# 780-00029_rev3_Pg1_Backplane_Instrument_.net
KiCad netlist of a schematic drawn in Altium Designer
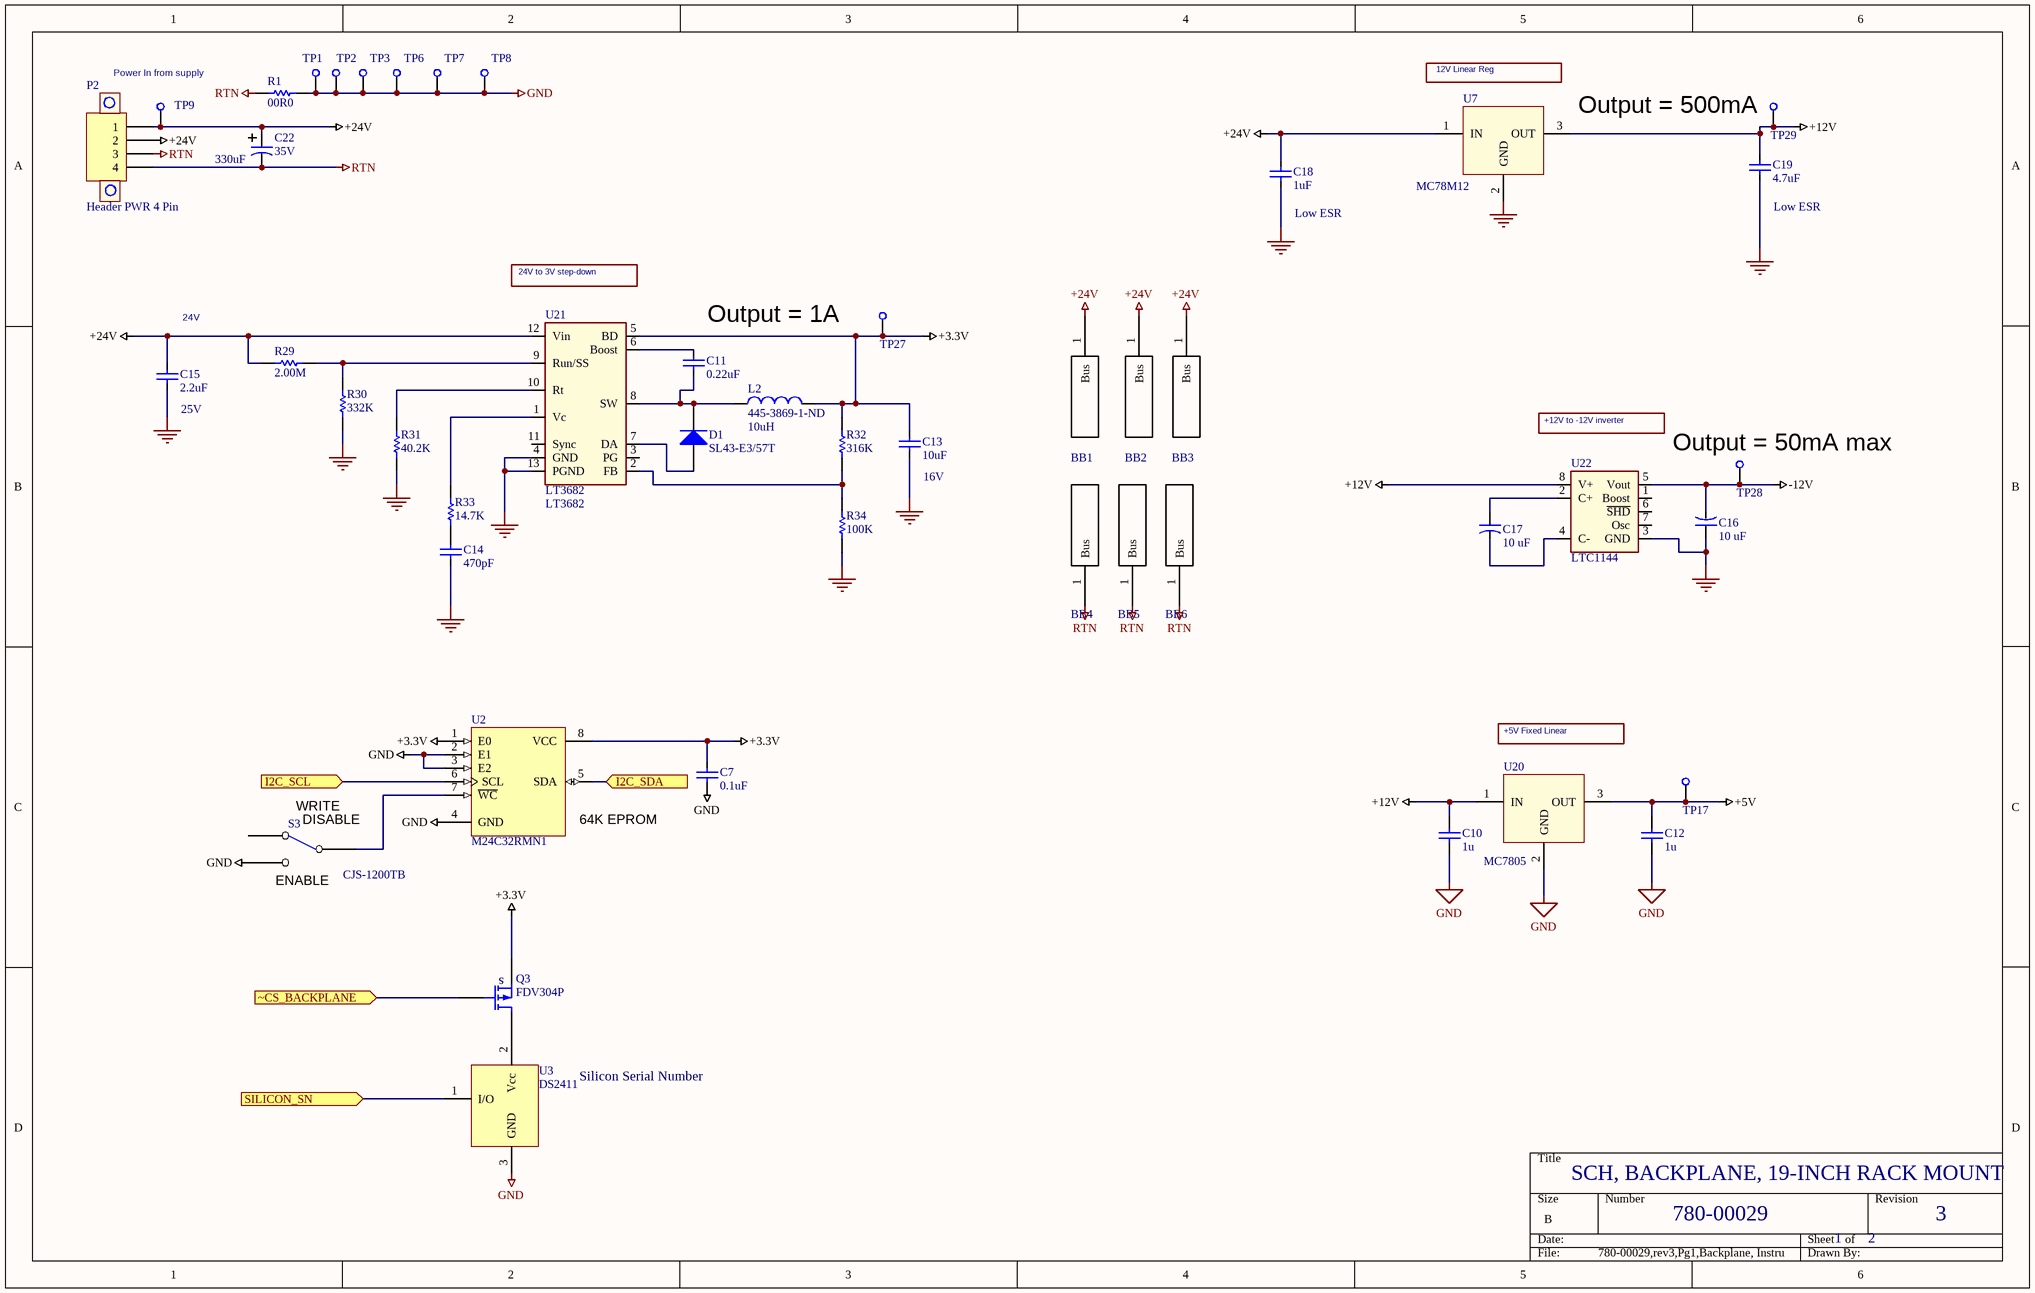
[diagram p0: 780-00029,rev3,Pg1,Backplane, Instrument Crate.SchDoc]

(export (version "E")
  (design (tool "Eeschema 10.0.6"))
  (components
    (comp (ref "BB1")
      (value "Bus Bar")
      (footprint "Bus Bar 1.5\" pitch")
      (fields (field (name "MANUFACTURER") "Circuit Components Inc."))
      (libsource (lib "Richs Schematic Components") (part "Bus Bar"))
    )
    (comp (ref "BB2")
      (value "Bus Bar")
      (footprint "Bus Bar 1.5\" pitch")
      (fields (field (name "MANUFACTURER") "Circuit Components Inc."))
      (libsource (lib "Richs Schematic Components") (part "Bus Bar"))
    )
    (comp (ref "BB3")
      (value "Bus Bar")
      (footprint "Bus Bar 1.5\" pitch")
      (fields (field (name "MANUFACTURER") "Circuit Components Inc."))
      (libsource (lib "Richs Schematic Components") (part "Bus Bar"))
    )
    (comp (ref "BB4")
      (value "Bus Bar")
      (footprint "Bus Bar 1.5\" pitch")
      (fields (field (name "MANUFACTURER") "Circuit Components Inc."))
      (libsource (lib "Richs Schematic Components") (part "Bus Bar"))
    )
    (comp (ref "BB5")
      (value "Bus Bar")
      (footprint "Bus Bar 1.5\" pitch")
      (fields (field (name "MANUFACTURER") "Circuit Components Inc."))
      (libsource (lib "Richs Schematic Components") (part "Bus Bar"))
    )
    (comp (ref "BB6")
      (value "Bus Bar")
      (footprint "Bus Bar 1.5\" pitch")
      (fields (field (name "MANUFACTURER") "Circuit Components Inc."))
      (libsource (lib "Richs Schematic Components") (part "Bus Bar"))
    )
    (comp (ref "C7")
      (value "0.1uF")
      (footprint "SMD_0805")
      (description "Capacitor")
      (fields (field (name "MANUFACTURER") "AVX") (field (name "Comment") "Cap SMD"))
      (libsource (lib "Richs Schematic Components") (part "Cap SMD"))
    )
    (comp (ref "C10")
      (value "1u")
      (footprint "2012[0805]")
      (description "Capacitor")
      (fields (field (name "MANUFACTURER") "Taiyo Yuden"))
      (libsource (lib "Miscellaneous Devices") (part "Cap"))
    )
    (comp (ref "C11")
      (value "0.22uF")
      (footprint "SMD_0805")
      (description "Capacitor")
      (fields (field (name "Comment") "Cap SMD"))
      (libsource (lib "Richs Schematic Components") (part "Cap SMD"))
    )
    (comp (ref "C12")
      (value "1u")
      (footprint "2012[0805]")
      (description "Capacitor")
      (fields (field (name "MANUFACTURER") "Taiyo Yuden"))
      (libsource (lib "Miscellaneous Devices") (part "Cap"))
    )
    (comp (ref "C13")
      (value "16V")
      (footprint "SMD_0805")
      (description "Capacitor")
      (fields (field (name "ALTIUM_VALUE") "10uF"))
      (libsource (lib "Richs Schematic Components") (part "Cap SMD"))
    )
    (comp (ref "C14")
      (value "470pF")
      (footprint "SMD_0805")
      (description "Capacitor")
      (fields (field (name "Comment") "Cap SMD"))
      (libsource (lib "Richs Schematic Components") (part "Cap SMD"))
    )
    (comp (ref "C15")
      (value "25V")
      (footprint "SMD_0805")
      (description "Capacitor")
      (fields (field (name "MANUFACTURER") "Taiyo Yuden") (field (name "ALTIUM_VALUE") "2.2uF"))
      (libsource (lib "Richs Schematic Components") (part "Cap SMD"))
    )
    (comp (ref "C16")
      (value "10 uF")
      (footprint "SMD_CAP_3216")
      (description "outline 3.2mm x 1.6mm")
      (fields (field (name "MANUFACTURER") "KEMET") (field (name "Comment") "16V"))
      (libsource (lib "Richs Schematic Components") (part "Cap Tant 16V"))
    )
    (comp (ref "C17")
      (value "10 uF")
      (footprint "SMD_CAP_3216")
      (description "outline 3.2mm x 1.6mm")
      (fields (field (name "MANUFACTURER") "KEMET") (field (name "Comment") "16V"))
      (libsource (lib "Richs Schematic Components") (part "Cap Tant 16V"))
    )
    (comp (ref "C18")
      (value "Low ESR")
      (footprint "SMD_1206")
      (description "Capacitor")
      (fields (field (name "MANUFACTURER") "TDK") (field (name "ALTIUM_VALUE") "1uF"))
      (libsource (lib "Richs Schematic Components") (part "Cap SMD"))
    )
    (comp (ref "C19")
      (value "Low ESR")
      (footprint "SMD_1206")
      (description "Capacitor")
      (fields (field (name "MANUFACTURER") "TDK") (field (name "ALTIUM_VALUE") "4.7uF"))
      (libsource (lib "Richs Schematic Components") (part "Cap SMD"))
    )
    (comp (ref "C22")
      (value "35V")
      (footprint "CAP, Thru Hole 10mm dia")
      (description "Radial Thru hole")
      (fields (field (name "ALTIUM_VALUE") "330uF"))
      (libsource (lib "Richs Schematic Components") (part "Cap Elec, 330 uF, 35V"))
    )
    (comp (ref "D1")
      (value "SL43-E3/57T")
      (footprint "DO-214AB")
      (description "Default Diode")
      (fields (field (name "MANUFACTURER") "Vishay/Dale"))
      (libsource (lib "Miscellaneous Devices") (part "Diode"))
    )
    (comp (ref "L2")
      (value "445-3869-1-ND")
      (footprint "Inductor TDC SLF")
      (description "Inductor")
      (fields (field (name "MANUFACTURER") "TDK") (field (name "ALTIUM_VALUE") "10uH"))
      (libsource (lib "Richs Schematic Components") (part "Inductor SMD 10uH 1.8A"))
    )
    (comp (ref "P2")
      (value "Header PWR 4 Pin")
      (footprint "HDR-4 pin w/screw")
      (description "Header, 4-Pin")
      (fields (field (name "MANUFACTURER") "tyco"))
      (libsource (lib "Richs Schematic Components") (part "Header 4 PWR"))
    )
    (comp (ref "Q3")
      (value "FDV304P")
      (footprint "SMD_SOT23_3")
      (description "P-MOSFET LOGIC LEVEL")
      (fields (field (name "MANUFACTURER") "Fairchild"))
      (libsource (lib "Richs Schematic Components") (part "FDV304P"))
    )
    (comp (ref "R1")
      (value "00R0")
      (footprint "SMD_0805")
      (description "Resistor 0805")
      (fields (field (name "MANUFACTURER") "Vishay/Dale") (field (name "Comment") "Res 0805"))
      (libsource (lib "Richs Schematic Components") (part "Res SMD"))
    )
    (comp (ref "R29")
      (value "2.00M")
      (footprint "SMD_0805")
      (description "Resistor 0805")
      (fields (field (name "MANUFACTURER") "Vishay/Dale") (field (name "Comment") "Res 0805"))
      (libsource (lib "Richs Schematic Components") (part "Res SMD"))
    )
    (comp (ref "R30")
      (value "332K")
      (footprint "SMD_0805")
      (description "Resistor 0805")
      (fields (field (name "MANUFACTURER") "Vishay/Dale") (field (name "Comment") "Res 0805"))
      (libsource (lib "Richs Schematic Components") (part "Res SMD"))
    )
    (comp (ref "R31")
      (value "40.2K")
      (footprint "SMD_0805")
      (description "Resistor 0805")
      (fields (field (name "MANUFACTURER") "Vishay/Dale") (field (name "Comment") "Res 0805"))
      (libsource (lib "Richs Schematic Components") (part "Res SMD"))
    )
    (comp (ref "R32")
      (value "316K")
      (footprint "SMD_0805")
      (description "Resistor 0805")
      (fields (field (name "MANUFACTURER") "Vishay/Dale") (field (name "Comment") "Res 0805"))
      (libsource (lib "Richs Schematic Components") (part "Res SMD"))
    )
    (comp (ref "R33")
      (value "14.7K")
      (footprint "SMD_0805")
      (description "Resistor 0805")
      (fields (field (name "MANUFACTURER") "Vishay/Dale") (field (name "Comment") "Res 0805"))
      (libsource (lib "Richs Schematic Components") (part "Res SMD"))
    )
    (comp (ref "R34")
      (value "100K")
      (footprint "SMD_0805")
      (description "Resistor 0805")
      (fields (field (name "MANUFACTURER") "Vishay/Dale") (field (name "Comment") "Res 0805"))
      (libsource (lib "Richs Schematic Components") (part "Res SMD"))
    )
    (comp (ref "S3")
      (value "CJS-1200TB")
      (footprint "CAS-120B")
      (fields (field (name "MANUFACTURER") "Copal Electronics"))
      (libsource (lib "JON_1_Library") (part "SW_SPDT_DOUG"))
    )
    (comp (ref "TP1")
      (value "Test point")
      (footprint "Protel 99SE BANKS PCB:PAD_80D_052H")
      (description "Test Point")
      (fields (field (name "MANUFACTURER") "Keystone"))
      (libsource (lib "Richs Schematic Components") (part "Test point"))
    )
    (comp (ref "TP2")
      (value "Test point")
      (footprint "Protel 99SE BANKS PCB:PAD_80D_052H")
      (description "Test Point")
      (fields (field (name "MANUFACTURER") "Keystone"))
      (libsource (lib "Richs Schematic Components") (part "Test point"))
    )
    (comp (ref "TP3")
      (value "Test point")
      (footprint "Protel 99SE BANKS PCB:PAD_80D_052H")
      (description "Test Point")
      (fields (field (name "MANUFACTURER") "Keystone"))
      (libsource (lib "Richs Schematic Components") (part "Test point"))
    )
    (comp (ref "TP6")
      (value "Test point")
      (footprint "Protel 99SE BANKS PCB:PAD_80D_052H")
      (description "Test Point")
      (fields (field (name "MANUFACTURER") "Keystone"))
      (libsource (lib "Richs Schematic Components") (part "Test point"))
    )
    (comp (ref "TP7")
      (value "Test point")
      (footprint "Protel 99SE BANKS PCB:PAD_80D_052H")
      (description "Test Point")
      (fields (field (name "MANUFACTURER") "Keystone"))
      (libsource (lib "Richs Schematic Components") (part "Test point"))
    )
    (comp (ref "TP8")
      (value "Test point")
      (footprint "Protel 99SE BANKS PCB:PAD_80D_052H")
      (description "Test Point")
      (fields (field (name "MANUFACTURER") "Keystone"))
      (libsource (lib "Richs Schematic Components") (part "Test point"))
    )
    (comp (ref "TP9")
      (value "Test Point SMD")
      (footprint "SMD_TEST POINT")
      (description "SMD loop test point")
      (libsource (lib "Richs Schematic Components") (part "Test Point SMD"))
    )
    (comp (ref "TP17")
      (value "Test Point SMD")
      (footprint "SMD_TEST POINT")
      (description "SMD loop test point")
      (libsource (lib "Richs Schematic Components") (part "Test Point SMD"))
    )
    (comp (ref "TP27")
      (value "Test Point SMD")
      (footprint "SMD_TEST POINT")
      (description "SMD loop test point")
      (libsource (lib "Richs Schematic Components") (part "Test Point SMD"))
    )
    (comp (ref "TP28")
      (value "Test Point SMD")
      (footprint "SMD_TEST POINT")
      (description "SMD loop test point")
      (libsource (lib "Richs Schematic Components") (part "Test Point SMD"))
    )
    (comp (ref "TP29")
      (value "Test Point SMD")
      (footprint "SMD_TEST POINT")
      (description "SMD loop test point")
      (libsource (lib "Richs Schematic Components") (part "Test Point SMD"))
    )
    (comp (ref "U2")
      (value "M24C32RMN1")
      (footprint "SOP8_N")
      (description "32 Kbit Serial I²C Bus EEPROM")
      (libsource (lib "ST Memory EEPROM Serial") (part "M24C32RMN1"))
    )
    (comp (ref "U3")
      (value "DS2411")
      (footprint "SMD_SOT23_3")
      (description "Silicon Serial Number")
      (fields (field (name "MANUFACTURER") "MAXIM"))
      (libsource (lib "Richs Schematic Components") (part "DS2411"))
    )
    (comp (ref "U7")
      (value "MC78M12")
      (footprint "TO-252(D-PAK)  PowerPAD")
      (fields (field (name "MANUFACTURER") "On Semi") (field (name "Comment") "Voltage Reg, Fixed"))
      (libsource (lib "Richs Schematic Components") (part "Voltage Reg, Fixed"))
    )
    (comp (ref "U20")
      (value "MC7805")
      (footprint "TO-252(D-PAK)  PowerPAD")
      (description "MC78M05")
      (fields (field (name "MANUFACTURER") "Fairchild") (field (name "Comment") "Voltage Reg, Fixed"))
      (libsource (lib "Richs Schematic Components") (part "Voltage Reg, Fixed"))
    )
    (comp (ref "U21")
      (value "LT3682")
      (footprint "DD12/DFN12")
      (description "1A uPwr Step-Down switching regulator")
      (fields (field (name "MANUFACTURER") "Linear") (field (name "ALTIUM_VALUE") "LT3682"))
      (libsource (lib "Richs Schematic Components") (part "LT3682"))
    )
    (comp (ref "U22")
      (value "LTC1144")
      (footprint "S8_M")
      (description "IC VOLT CONV SW-CAP W/SHTDN8SOIC")
      (fields (field (name "MANUFACTURER") "Linear"))
      (libsource (lib "Richs Schematic Components") (part "LTC1144"))
    )
  )
  (nets
    (net (code "1") (name "+3.3V") (class "Default")
      (node (ref "C13") (pin "2") (pinfunction "2_2") (pintype "passive"))
      (node (ref "C7") (pin "2") (pinfunction "2_2") (pintype "passive"))
      (node (ref "L2") (pin "2") (pinfunction "2_2") (pintype "passive"))
      (node (ref "Q3") (pin "2") (pinfunction "S_2") (pintype "passive"))
      (node (ref "R32") (pin "2") (pinfunction "2_2") (pintype "passive"))
      (node (ref "TP27") (pin "1") (pinfunction "TP_1") (pintype "passive"))
      (node (ref "U2") (pin "1") (pinfunction "E0_1") (pintype "input"))
      (node (ref "U2") (pin "8") (pinfunction "VCC_8") (pintype "power_in"))
      (node (ref "U21") (pin "5") (pinfunction "BD_5") (pintype "passive"))
    )
    (net (code "2") (name "+5V") (class "Default")
      (node (ref "C12") (pin "1") (pinfunction "1_1") (pintype "passive"))
      (node (ref "TP17") (pin "1") (pinfunction "TP_1") (pintype "passive"))
      (node (ref "U20") (pin "3") (pinfunction "OUT_3") (pintype "passive"))
    )
    (net (code "3") (name "+12V") (class "Default")
      (node (ref "C10") (pin "1") (pinfunction "1_1") (pintype "passive"))
      (node (ref "C19") (pin "2") (pinfunction "2_2") (pintype "passive"))
      (node (ref "TP29") (pin "1") (pinfunction "TP_1") (pintype "passive"))
      (node (ref "U20") (pin "1") (pinfunction "IN_1") (pintype "passive"))
      (node (ref "U22") (pin "8") (pinfunction "V+_8") (pintype "power_in"))
      (node (ref "U7") (pin "3") (pinfunction "OUT_3") (pintype "passive"))
    )
    (net (code "4") (name "+24V") (class "Default")
      (node (ref "BB1") (pin "1") (pinfunction "Bus_1") (pintype "passive"))
      (node (ref "BB2") (pin "1") (pinfunction "Bus_1") (pintype "passive"))
      (node (ref "BB3") (pin "1") (pinfunction "Bus_1") (pintype "passive"))
      (node (ref "C15") (pin "2") (pinfunction "2_2") (pintype "passive"))
      (node (ref "C18") (pin "2") (pinfunction "2_2") (pintype "passive"))
      (node (ref "C22") (pin "1") (pinfunction "1_1") (pintype "passive"))
      (node (ref "P2") (pin "1") (pinfunction "1_1") (pintype "passive"))
      (node (ref "P2") (pin "2") (pinfunction "2_2") (pintype "passive"))
      (node (ref "R29") (pin "1") (pinfunction "1_1") (pintype "passive"))
      (node (ref "TP9") (pin "1") (pinfunction "TP_1") (pintype "passive"))
      (node (ref "U21") (pin "12") (pinfunction "Vin_12") (pintype "passive"))
      (node (ref "U7") (pin "1") (pinfunction "IN_1") (pintype "passive"))
    )
    (net (code "5") (name "-12V") (class "Default")
      (node (ref "C16") (pin "2") (pinfunction "2_2") (pintype "passive"))
      (node (ref "TP28") (pin "1") (pinfunction "TP_1") (pintype "passive"))
      (node (ref "U22") (pin "5") (pinfunction "Vout_5") (pintype "passive"))
    )
    (net (code "6") (name "/I2C_SCL") (class "Default")
      (node (ref "U2") (pin "6") (pinfunction "SCL_6") (pintype "input"))
    )
    (net (code "7") (name "/I2C_SDA") (class "Default")
      (node (ref "U2") (pin "5") (pinfunction "SDA_5") (pintype "bidirectional"))
    )
    (net (code "8") (name "/SILICON_SN") (class "Default")
      (node (ref "U3") (pin "1") (pinfunction "I/O_1") (pintype "passive"))
    )
    (net (code "9") (name "/~CS_BACKPLANE") (class "Default")
      (node (ref "Q3") (pin "1") (pinfunction "G_1") (pintype "passive"))
    )
    (net (code "10") (name "GND") (class "Default")
      (node (ref "C10") (pin "2") (pinfunction "2_2") (pintype "passive"))
      (node (ref "C12") (pin "2") (pinfunction "2_2") (pintype "passive"))
      (node (ref "C13") (pin "1") (pinfunction "1_1") (pintype "passive"))
      (node (ref "C14") (pin "1") (pinfunction "1_1") (pintype "passive"))
      (node (ref "C15") (pin "1") (pinfunction "1_1") (pintype "passive"))
      (node (ref "C16") (pin "1") (pinfunction "1_1") (pintype "passive"))
      (node (ref "C18") (pin "1") (pinfunction "1_1") (pintype "passive"))
      (node (ref "C19") (pin "1") (pinfunction "1_1") (pintype "passive"))
      (node (ref "C7") (pin "1") (pinfunction "1_1") (pintype "passive"))
      (node (ref "R1") (pin "2") (pinfunction "2_2") (pintype "passive"))
      (node (ref "R30") (pin "1") (pinfunction "1_1") (pintype "passive"))
      (node (ref "R31") (pin "1") (pinfunction "1_1") (pintype "passive"))
      (node (ref "R34") (pin "1") (pinfunction "1_1") (pintype "passive"))
      (node (ref "S3") (pin "1") (pinfunction "NO_1") (pintype "passive"))
      (node (ref "TP1") (pin "1") (pinfunction "TP_1") (pintype "passive"))
      (node (ref "TP2") (pin "1") (pinfunction "TP_1") (pintype "passive"))
      (node (ref "TP3") (pin "1") (pinfunction "TP_1") (pintype "passive"))
      (node (ref "TP6") (pin "1") (pinfunction "TP_1") (pintype "passive"))
      (node (ref "TP7") (pin "1") (pinfunction "TP_1") (pintype "passive"))
      (node (ref "TP8") (pin "1") (pinfunction "TP_1") (pintype "passive"))
      (node (ref "U2") (pin "2") (pinfunction "E1_2") (pintype "input"))
      (node (ref "U2") (pin "3") (pinfunction "E2_3") (pintype "input"))
      (node (ref "U2") (pin "4") (pinfunction "GND_4") (pintype "power_in"))
      (node (ref "U20") (pin "2") (pinfunction "GND_2") (pintype "passive"))
      (node (ref "U21") (pin "13") (pinfunction "PGND_13") (pintype "passive"))
      (node (ref "U21") (pin "4") (pinfunction "GND_4") (pintype "power_in"))
      (node (ref "U22") (pin "3") (pinfunction "GND_3") (pintype "passive"))
      (node (ref "U3") (pin "3") (pinfunction "GND_3") (pintype "passive"))
      (node (ref "U7") (pin "2") (pinfunction "GND_2") (pintype "passive"))
    )
    (net (code "11") (name "Net-(C14-Pad2)") (class "Default")
      (node (ref "C14") (pin "2") (pinfunction "2_2") (pintype "passive"))
      (node (ref "R33") (pin "1") (pinfunction "1_1") (pintype "passive"))
    )
    (net (code "12") (name "Net-(D1-A)") (class "Default")
      (node (ref "D1") (pin "1") (pinfunction "A_1") (pintype "passive"))
      (node (ref "U21") (pin "7") (pinfunction "DA_7") (pintype "passive"))
    )
    (net (code "13") (name "Net-(D1-K)") (class "Default")
      (node (ref "C11") (pin "1") (pinfunction "1_1") (pintype "passive"))
      (node (ref "D1") (pin "2") (pinfunction "K_2") (pintype "passive"))
      (node (ref "L2") (pin "1") (pinfunction "1_1") (pintype "passive"))
      (node (ref "U21") (pin "8") (pinfunction "SW_8") (pintype "passive"))
    )
    (net (code "14") (name "Net-(Q3-D)") (class "Default")
      (node (ref "Q3") (pin "3") (pinfunction "D_3") (pintype "passive"))
      (node (ref "U3") (pin "2") (pinfunction "Vcc_2") (pintype "passive"))
    )
    (net (code "15") (name "Net-(S3-COM)") (class "Default")
      (node (ref "S3") (pin "2") (pinfunction "COM_2") (pintype "passive"))
      (node (ref "U2") (pin "7") (pinfunction "~{WC}_7") (pintype "input"))
    )
    (net (code "16") (name "Net-(U21-Boost)") (class "Default")
      (node (ref "C11") (pin "2") (pinfunction "2_2") (pintype "passive"))
      (node (ref "U21") (pin "6") (pinfunction "Boost_6") (pintype "passive"))
    )
    (net (code "17") (name "Net-(U21-FB)") (class "Default")
      (node (ref "R32") (pin "1") (pinfunction "1_1") (pintype "passive"))
      (node (ref "R34") (pin "2") (pinfunction "2_2") (pintype "passive"))
      (node (ref "U21") (pin "2") (pinfunction "FB_2") (pintype "passive"))
    )
    (net (code "18") (name "Net-(U21-Rt)") (class "Default")
      (node (ref "R31") (pin "2") (pinfunction "2_2") (pintype "passive"))
      (node (ref "U21") (pin "10") (pinfunction "Rt_10") (pintype "passive"))
    )
    (net (code "19") (name "Net-(U21-Run{slash}SS)") (class "Default")
      (node (ref "R29") (pin "2") (pinfunction "2_2") (pintype "passive"))
      (node (ref "R30") (pin "2") (pinfunction "2_2") (pintype "passive"))
      (node (ref "U21") (pin "9") (pinfunction "Run/SS_9") (pintype "passive"))
    )
    (net (code "20") (name "Net-(U21-Vc)") (class "Default")
      (node (ref "R33") (pin "2") (pinfunction "2_2") (pintype "passive"))
      (node (ref "U21") (pin "1") (pinfunction "Vc_1") (pintype "passive"))
    )
    (net (code "21") (name "Net-(U22-C+)") (class "Default")
      (node (ref "C17") (pin "1") (pinfunction "1_1") (pintype "passive"))
      (node (ref "U22") (pin "2") (pinfunction "C+_2") (pintype "passive"))
    )
    (net (code "22") (name "Net-(U22-C-)") (class "Default")
      (node (ref "C17") (pin "2") (pinfunction "2_2") (pintype "passive"))
      (node (ref "U22") (pin "4") (pinfunction "C-_4") (pintype "passive"))
    )
    (net (code "23") (name "RTN") (class "Default")
      (node (ref "BB4") (pin "1") (pinfunction "Bus_1") (pintype "passive"))
      (node (ref "BB5") (pin "1") (pinfunction "Bus_1") (pintype "passive"))
      (node (ref "BB6") (pin "1") (pinfunction "Bus_1") (pintype "passive"))
      (node (ref "C22") (pin "2") (pinfunction "2_2") (pintype "passive"))
      (node (ref "P2") (pin "3") (pinfunction "3_3") (pintype "passive"))
      (node (ref "P2") (pin "4") (pinfunction "4_4") (pintype "passive"))
      (node (ref "R1") (pin "1") (pinfunction "1_1") (pintype "passive"))
    )
    (net (code "24") (name "unconnected-(S3-NC-Pad3)") (class "Default")
      (node (ref "S3") (pin "3") (pinfunction "NC_3") (pintype "passive"))
    )
    (net (code "25") (name "unconnected-(U21-PG-Pad3)") (class "Default")
      (node (ref "U21") (pin "3") (pinfunction "PG_3") (pintype "passive"))
    )
    (net (code "26") (name "unconnected-(U21-Sync-Pad11)") (class "Default")
      (node (ref "U21") (pin "11") (pinfunction "Sync_11") (pintype "passive"))
    )
    (net (code "27") (name "unconnected-(U22-Boost-Pad1)") (class "Default")
      (node (ref "U22") (pin "1") (pinfunction "Boost_1") (pintype "passive"))
    )
    (net (code "28") (name "unconnected-(U22-Osc-Pad7)") (class "Default")
      (node (ref "U22") (pin "7") (pinfunction "Osc_7") (pintype "passive"))
    )
    (net (code "29") (name "unconnected-(U22-~{SHD}-Pad6)") (class "Default")
      (node (ref "U22") (pin "6") (pinfunction "~{SHD}_6") (pintype "passive"))
    )
  )
)
